# USB.net
KiCad netlist of a schematic drawn in Altium Designer
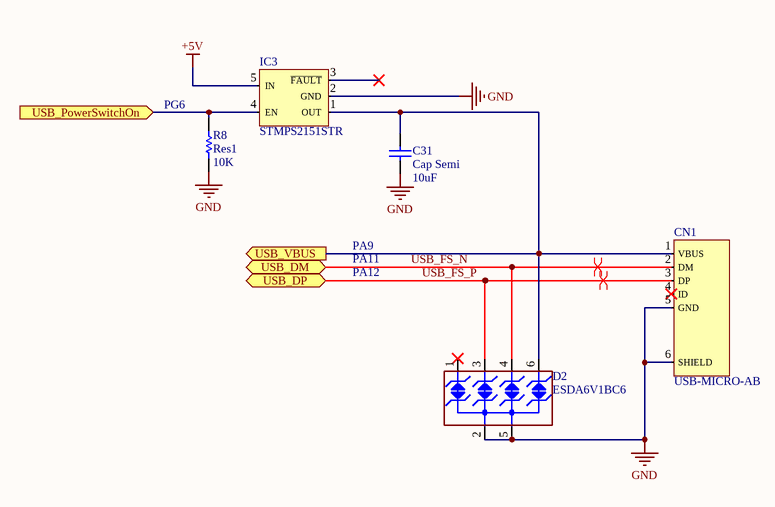
[diagram p0: USB.SchDoc]

(export (version "E")
  (design (tool "Eeschema 10.0.6"))
  (components
    (comp (ref "C31")
      (value "Cap Semi")
      (footprint "CAP_TANT1206")
      (description "Tantalum Capacitors - Solid SMD 16V 10uF 1206 10% ESR=3Ohms")
      (fields (field (name "ALTIUM_VALUE") "10uF"))
      (libsource (lib "Miscellaneous Devices") (part "Cap Semi"))
    )
    (comp (ref "CN1")
      (value "USB-MICRO-AB")
      (footprint "USB-MICRO-AB")
      (description "USB Connectors WR-COM USB Micro SMT Type AB Horiztl")
      (libsource (lib "MainboardSchLib") (part "USB-MICRO-AB"))
    )
    (comp (ref "D2")
      (value "ESDA6V1BC6")
      (footprint "SOT23-6L")
      (description "ESD Suppressors / TVS Diodes 6.1V 80W Bidirect")
      (libsource (lib "MainboardSchLib") (part "ESDA6V1BC6"))
    )
    (comp (ref "IC3")
      (value "STMPS2151STR")
      (footprint "SOT23-5L")
      (description "Power Switch ICs - Power Distribution SGL CHNL PWR SWTCH")
      (libsource (lib "MainboardSchLib") (part "STMPS215"))
    )
    (comp (ref "R8")
      (value "Res1")
      (footprint "RES0402")
      (description "Thick Film Resistors - SMD 0.2watt 10Kohms 1% 100ppm")
      (fields (field (name "ALTIUM_VALUE") "10K"))
      (libsource (lib "Miscellaneous Devices") (part "Res1"))
    )
  )
  (nets
    (net (code "1") (name "+5V") (class "Default")
      (node (ref "IC3") (pin "5") (pinfunction "IN_5") (pintype "input"))
    )
    (net (code "2") (name "/USB_FS_N") (class "Default")
      (node (ref "CN1") (pin "2") (pinfunction "DM_2") (pintype "passive"))
      (node (ref "D2") (pin "4") (pinfunction "IO3_4") (pintype "passive"))
    )
    (net (code "3") (name "/USB_FS_P") (class "Default")
      (node (ref "CN1") (pin "3") (pinfunction "DP_3") (pintype "passive"))
      (node (ref "D2") (pin "3") (pinfunction "GND_3") (pintype "passive"))
    )
    (net (code "4") (name "/USB_PowerSwitchOn") (class "Default")
      (node (ref "IC3") (pin "4") (pinfunction "EN_4") (pintype "input"))
      (node (ref "R8") (pin "2") (pinfunction "2_2") (pintype "passive"))
    )
    (net (code "5") (name "/USB_VBUS") (class "Default")
      (node (ref "C31") (pin "2") (pinfunction "2_2") (pintype "passive"))
      (node (ref "CN1") (pin "1") (pinfunction "VBUS_1") (pintype "passive"))
      (node (ref "D2") (pin "6") (pinfunction "NC_6") (pintype "passive"))
      (node (ref "IC3") (pin "1") (pinfunction "OUT_1") (pintype "output"))
    )
    (net (code "6") (name "GND") (class "Default")
      (node (ref "C31") (pin "1") (pinfunction "1_1") (pintype "passive"))
      (node (ref "CN1") (pin "5") (pinfunction "GND_5") (pintype "passive"))
      (node (ref "CN1") (pin "6") (pinfunction "SHIELD_6") (pintype "passive"))
      (node (ref "D2") (pin "2") (pinfunction "IO2_2") (pintype "passive"))
      (node (ref "D2") (pin "5") (pinfunction "IO4_5") (pintype "passive"))
      (node (ref "IC3") (pin "2") (pinfunction "GND_2") (pintype "power_in"))
      (node (ref "R8") (pin "1") (pinfunction "1_1") (pintype "passive"))
    )
    (net (code "7") (name "unconnected-(CN1-ID-Pad4)") (class "Default")
      (node (ref "CN1") (pin "4") (pinfunction "ID_4") (pintype "passive+no_connect"))
    )
    (net (code "8") (name "unconnected-(D2-IO1-Pad1)") (class "Default")
      (node (ref "D2") (pin "1") (pinfunction "IO1_1") (pintype "passive+no_connect"))
    )
    (net (code "9") (name "unconnected-(IC3-~{FAULT}-Pad3)") (class "Default")
      (node (ref "IC3") (pin "3") (pinfunction "~{FAULT}_3") (pintype "output+no_connect"))
    )
  )
)
